# CAN.net
KiCad netlist of a schematic drawn in Altium Designer
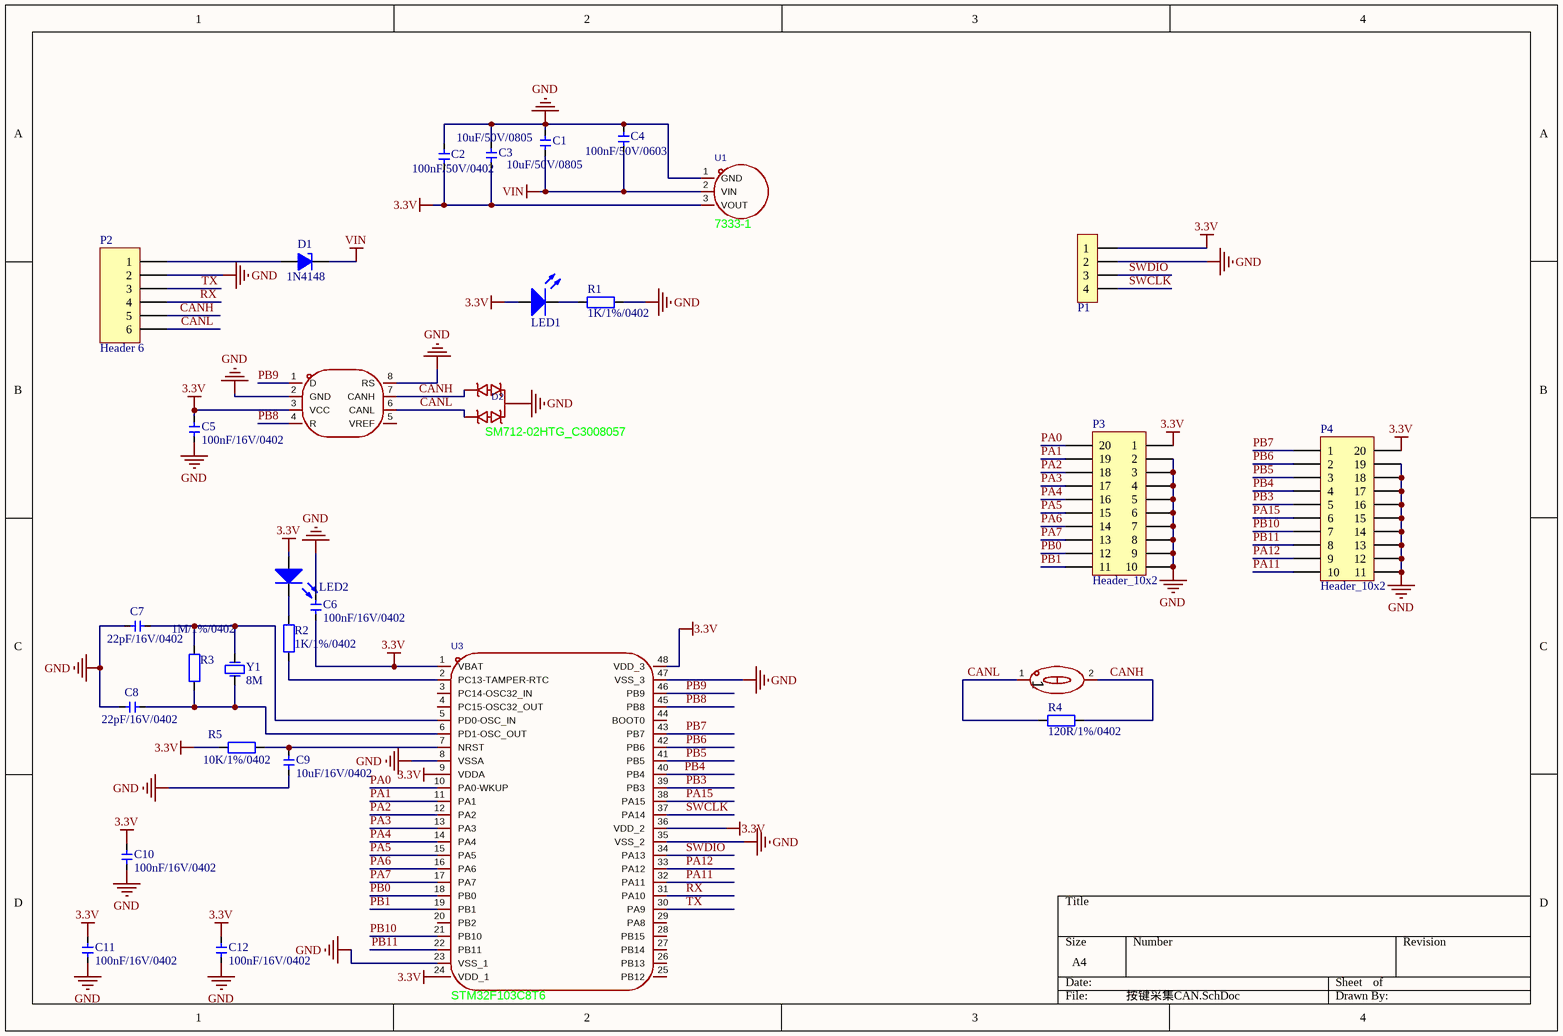
[diagram p0: 按键采集CAN.SchDoc]

(export (version "E")
  (design (tool "Eeschema 10.0.6"))
  (components
    (comp (ref "C1")
      (value "10uF/50V/0805")
      (footprint "CAP-0805")
      (description "无极性电容")
      (fields (field (name "PUBLISHER") "Altium Limited"))
      (libsource (lib "Arrowy_Racing") (part "Cap"))
    )
    (comp (ref "C2")
      (value "100nF/50V/0402")
      (footprint "0402")
      (description "无极性电容")
      (fields (field (name "PUBLISHER") "Altium Limited"))
      (libsource (lib "Arrowy_Racing") (part "Cap"))
    )
    (comp (ref "C3")
      (value "10uF/50V/0805")
      (footprint "CAP-0805")
      (description "无极性电容")
      (fields (field (name "PUBLISHER") "Altium Limited"))
      (libsource (lib "Arrowy_Racing") (part "Cap"))
    )
    (comp (ref "C4")
      (value "100nF/50V/0603")
      (footprint "CAP-0603")
      (description "无极性电容")
      (fields (field (name "PUBLISHER") "Altium Limited"))
      (libsource (lib "Arrowy_Racing") (part "Cap"))
    )
    (comp (ref "C5")
      (value "100nF/16V/0402")
      (footprint "cap-0402")
      (description "无极性电容")
      (fields (field (name "PUBLISHER") "Altium Limited"))
      (libsource (lib "Arrowy_Racing") (part "Cap"))
    )
    (comp (ref "C6")
      (value "100nF/16V/0402")
      (footprint "cap-0402")
      (description "无极性电容")
      (fields (field (name "PUBLISHER") "Altium Limited"))
      (libsource (lib "Arrowy_Racing") (part "Cap"))
    )
    (comp (ref "C7")
      (value "22pF/16V/0402")
      (footprint "cap-0402")
      (description "无极性电容")
      (fields (field (name "PUBLISHER") "Altium Limited"))
      (libsource (lib "Arrowy_Racing") (part "Cap"))
    )
    (comp (ref "C8")
      (value "22pF/16V/0402")
      (footprint "cap-0402")
      (description "无极性电容")
      (fields (field (name "PUBLISHER") "Altium Limited"))
      (libsource (lib "Arrowy_Racing") (part "Cap"))
    )
    (comp (ref "C9")
      (value "10uF/16V/0402")
      (footprint "cap-0402")
      (description "无极性电容")
      (fields (field (name "PUBLISHER") "Altium Limited"))
      (libsource (lib "Arrowy_Racing") (part "Cap"))
    )
    (comp (ref "C10")
      (value "100nF/16V/0402")
      (footprint "cap-0402")
      (description "无极性电容")
      (fields (field (name "PUBLISHER") "Altium Limited"))
      (libsource (lib "Arrowy_Racing") (part "Cap"))
    )
    (comp (ref "C11")
      (value "100nF/16V/0402")
      (footprint "cap-0402")
      (description "无极性电容")
      (fields (field (name "PUBLISHER") "Altium Limited"))
      (libsource (lib "Arrowy_Racing") (part "Cap"))
    )
    (comp (ref "C12")
      (value "100nF/16V/0402")
      (footprint "cap-0402")
      (description "无极性电容")
      (fields (field (name "PUBLISHER") "Altium Limited"))
      (libsource (lib "Arrowy_Racing") (part "Cap"))
    )
    (comp (ref "D1")
      (value "1N4148")
      (footprint "SOD-123")
      (fields (field (name "PUBLISHER") "Altium Limited"))
      (libsource (lib "Arrowy_Racing") (part "Diode-Z"))
    )
    (comp (ref "D2")
      (value "SM712-02HTG_C3008057")
      (footprint "SOT-23-3_L2.9-W1.3-P1.90-LS2.4-BR")
      (libsource (lib "altium-import") (part "root_0_SM712-02HTG_C3008057_"))
    )
    (comp (ref "LED1")
      (value "red")
      (footprint "LED_0603")
      (description "发光二极管")
      (fields (field (name "PUBLISHER") "Altium Limited"))
      (libsource (lib "Arrowy_Racing") (part "LED"))
    )
    (comp (ref "LED2")
      (value "green")
      (footprint "LED_0603")
      (description "发光二极管")
      (fields (field (name "PUBLISHER") "Altium Limited"))
      (libsource (lib "Arrowy_Racing") (part "LED"))
    )
    (comp (ref "P1")
      (value "Header 4")
      (footprint "HDR-SMD_4P-P2.54-H-M-W13.3-N")
      (description "接插件")
      (fields (field (name "PUBLISHER") "Altium Limited"))
      (libsource (lib "Arrowy_Racing") (part "Header 4"))
    )
    (comp (ref "P2")
      (value "Header 6")
      (footprint "CONN-TH_6P-P2.50_HC-XH-6AW-G")
      (description "Header, 6-Pin")
      (fields (field (name "PUBLISHER") "Altium Limited"))
      (libsource (lib "Miscellaneous Connectors") (part "Header 6"))
    )
    (comp (ref "P3")
      (value "Header_10x2")
      (footprint "HDR-TH_20P-P2.54-V-M-R2-C10-S2.54")
      (description "接插件")
      (libsource (lib "Arrowy_Racing") (part "Header_10x2"))
    )
    (comp (ref "P4")
      (value "Header_10x2")
      (footprint "HDR-TH_20P-P2.54-V-M-R2-C10-S2.54")
      (description "接插件")
      (libsource (lib "") (part "Header_10x2_1"))
    )
    (comp (ref "R1")
      (value "1K/1%/0402")
      (footprint "r0402")
      (description "贴片电阻")
      (fields (field (name "PUBLISHER") "Altium Limited"))
      (libsource (lib "Arrowy_Racing") (part "Res"))
    )
    (comp (ref "R2")
      (value "1K/1%/0402")
      (footprint "r0402")
      (description "贴片电阻")
      (fields (field (name "PUBLISHER") "Altium Limited"))
      (libsource (lib "") (part "Res_2"))
    )
    (comp (ref "R3")
      (value "1M/1%/0402")
      (footprint "r0402")
      (description "贴片电阻")
      (fields (field (name "PUBLISHER") "Altium Limited"))
      (libsource (lib "") (part "Res_2"))
    )
    (comp (ref "R4")
      (value "120R/1%/0402")
      (footprint "r0402")
      (description "贴片电阻")
      (fields (field (name "PUBLISHER") "Altium Limited"))
      (libsource (lib "") (part "Res_1"))
    )
    (comp (ref "R5")
      (value "10K/1%/0402")
      (footprint "r0402")
      (description "贴片电阻")
      (fields (field (name "PUBLISHER") "Altium Limited"))
      (libsource (lib "Arrowy_Racing") (part "Res"))
    )
    (comp (ref "SW1")
      (value "DSIC01LS-P_C600988")
      (footprint "SW-SMD_2P-L3.5-W6.1-P2.54-LS9.8")
      (libsource (lib "altium-import") (part "root_3_DSIC01LS-P_C600988_"))
    )
    (comp (ref "U1")
      (value "7333-1")
      (footprint "SOT89")
      (libsource (lib "altium-import") (part "root_0_7333-1_"))
    )
    (comp (ref "U2")
      (value "SN65HVD230DR")
      (footprint "SOIC-8_L4.9-W3.9-P1.27-LS6.0-BL")
      (libsource (lib "altium-import") (part "root_0_SN65HVD230DR_"))
    )
    (comp (ref "U3")
      (value "STM32F103C8T6")
      (footprint "LQFP48_STM32F103C")
      (libsource (lib "altium-import") (part "root_0_STM32F103C8T6_"))
    )
    (comp (ref "Y1")
      (value "8M")
      (footprint "CRYSTAL-SMD_L5.0-W3.2")
      (description "两脚无源晶振")
      (fields (field (name "Comment") "TAXM8M2QLFCDT1T") (field (name "PUBLISHER") "Altium Limited"))
      (libsource (lib "Arrowy_Racing") (part "Passive_Crystal_2Pin"))
    )
  )
  (nets
    (net (code "1") (name "/CANH") (class "Default")
      (node (ref "D2") (pin "1") (pinfunction "1_1") (pintype "passive"))
      (node (ref "P2") (pin "5") (pinfunction "5_5") (pintype "passive"))
      (node (ref "R4") (pin "2") (pinfunction "2_2") (pintype "passive"))
      (node (ref "SW1") (pin "2") (pinfunction "PIN2_2") (pintype "passive"))
      (node (ref "U2") (pin "7") (pinfunction "CANH_7") (pintype "passive"))
    )
    (net (code "2") (name "/CANL") (class "Default")
      (node (ref "D2") (pin "2") (pinfunction "2_2") (pintype "passive"))
      (node (ref "P2") (pin "6") (pinfunction "6_6") (pintype "passive"))
      (node (ref "R4") (pin "1") (pinfunction "1_1") (pintype "passive"))
      (node (ref "SW1") (pin "1") (pinfunction "PIN1_1") (pintype "passive"))
      (node (ref "U2") (pin "6") (pinfunction "CANL_6") (pintype "passive"))
    )
    (net (code "3") (name "/PA0") (class "Default")
      (node (ref "P3") (pin "20") (pinfunction "20_20") (pintype "passive"))
      (node (ref "U3") (pin "10") (pinfunction "PA0-WKUP_10") (pintype "passive"))
    )
    (net (code "4") (name "/PA1") (class "Default")
      (node (ref "P3") (pin "19") (pinfunction "19_19") (pintype "passive"))
      (node (ref "U3") (pin "11") (pinfunction "PA1_11") (pintype "passive"))
    )
    (net (code "5") (name "/PA2") (class "Default")
      (node (ref "P3") (pin "18") (pinfunction "18_18") (pintype "passive"))
      (node (ref "U3") (pin "12") (pinfunction "PA2_12") (pintype "passive"))
    )
    (net (code "6") (name "/PA3") (class "Default")
      (node (ref "P3") (pin "17") (pinfunction "17_17") (pintype "passive"))
      (node (ref "U3") (pin "13") (pinfunction "PA3_13") (pintype "passive"))
    )
    (net (code "7") (name "/PA4") (class "Default")
      (node (ref "P3") (pin "16") (pinfunction "16_16") (pintype "passive"))
      (node (ref "U3") (pin "14") (pinfunction "PA4_14") (pintype "passive"))
    )
    (net (code "8") (name "/PA5") (class "Default")
      (node (ref "P3") (pin "15") (pinfunction "15_15") (pintype "passive"))
      (node (ref "U3") (pin "15") (pinfunction "PA5_15") (pintype "passive"))
    )
    (net (code "9") (name "/PA6") (class "Default")
      (node (ref "P3") (pin "14") (pinfunction "14_14") (pintype "passive"))
      (node (ref "U3") (pin "16") (pinfunction "PA6_16") (pintype "passive"))
    )
    (net (code "10") (name "/PA7") (class "Default")
      (node (ref "P3") (pin "13") (pinfunction "13_13") (pintype "passive"))
      (node (ref "U3") (pin "17") (pinfunction "PA7_17") (pintype "passive"))
    )
    (net (code "11") (name "/PA11") (class "Default")
      (node (ref "P4") (pin "10") (pinfunction "10_10") (pintype "passive"))
      (node (ref "U3") (pin "32") (pinfunction "PA11_32") (pintype "passive"))
    )
    (net (code "12") (name "/PA12") (class "Default")
      (node (ref "P4") (pin "9") (pinfunction "9_9") (pintype "passive"))
      (node (ref "U3") (pin "33") (pinfunction "PA12_33") (pintype "passive"))
    )
    (net (code "13") (name "/PA15") (class "Default")
      (node (ref "P4") (pin "6") (pinfunction "6_6") (pintype "passive"))
      (node (ref "U3") (pin "38") (pinfunction "PA15_38") (pintype "passive"))
    )
    (net (code "14") (name "/PB0") (class "Default")
      (node (ref "P3") (pin "12") (pinfunction "12_12") (pintype "passive"))
      (node (ref "U3") (pin "18") (pinfunction "PB0_18") (pintype "passive"))
    )
    (net (code "15") (name "/PB1") (class "Default")
      (node (ref "P3") (pin "11") (pinfunction "11_11") (pintype "passive"))
      (node (ref "U3") (pin "19") (pinfunction "PB1_19") (pintype "passive"))
    )
    (net (code "16") (name "/PB3") (class "Default")
      (node (ref "P4") (pin "5") (pinfunction "5_5") (pintype "passive"))
      (node (ref "U3") (pin "39") (pinfunction "PB3_39") (pintype "passive"))
    )
    (net (code "17") (name "/PB4") (class "Default")
      (node (ref "P4") (pin "4") (pinfunction "4_4") (pintype "passive"))
      (node (ref "U3") (pin "40") (pinfunction "PB4_40") (pintype "passive"))
    )
    (net (code "18") (name "/PB5") (class "Default")
      (node (ref "P4") (pin "3") (pinfunction "3_3") (pintype "passive"))
      (node (ref "U3") (pin "41") (pinfunction "PB5_41") (pintype "passive"))
    )
    (net (code "19") (name "/PB6") (class "Default")
      (node (ref "P4") (pin "2") (pinfunction "2_2") (pintype "passive"))
      (node (ref "U3") (pin "42") (pinfunction "PB6_42") (pintype "passive"))
    )
    (net (code "20") (name "/PB7") (class "Default")
      (node (ref "P4") (pin "1") (pinfunction "1_1") (pintype "passive"))
      (node (ref "U3") (pin "43") (pinfunction "PB7_43") (pintype "passive"))
    )
    (net (code "21") (name "/PB8") (class "Default")
      (node (ref "U2") (pin "4") (pinfunction "R_4") (pintype "passive"))
      (node (ref "U3") (pin "45") (pinfunction "PB8_45") (pintype "passive"))
    )
    (net (code "22") (name "/PB9") (class "Default")
      (node (ref "U2") (pin "1") (pinfunction "D_1") (pintype "passive"))
      (node (ref "U3") (pin "46") (pinfunction "PB9_46") (pintype "passive"))
    )
    (net (code "23") (name "/PB10") (class "Default")
      (node (ref "P4") (pin "7") (pinfunction "7_7") (pintype "passive"))
      (node (ref "U3") (pin "21") (pinfunction "PB10_21") (pintype "passive"))
    )
    (net (code "24") (name "/PB11") (class "Default")
      (node (ref "P4") (pin "8") (pinfunction "8_8") (pintype "passive"))
      (node (ref "U3") (pin "22") (pinfunction "PB11_22") (pintype "passive"))
    )
    (net (code "25") (name "/RX") (class "Default")
      (node (ref "P2") (pin "4") (pinfunction "4_4") (pintype "passive"))
      (node (ref "U3") (pin "31") (pinfunction "PA10_31") (pintype "passive"))
    )
    (net (code "26") (name "/SWCLK") (class "Default")
      (node (ref "P1") (pin "4") (pinfunction "4_4") (pintype "passive"))
      (node (ref "U3") (pin "37") (pinfunction "PA14_37") (pintype "passive"))
    )
    (net (code "27") (name "/SWDIO") (class "Default")
      (node (ref "P1") (pin "3") (pinfunction "3_3") (pintype "passive"))
      (node (ref "U3") (pin "34") (pinfunction "PA13_34") (pintype "passive"))
    )
    (net (code "28") (name "/TX") (class "Default")
      (node (ref "P2") (pin "3") (pinfunction "3_3") (pintype "passive"))
      (node (ref "U3") (pin "30") (pinfunction "PA9_30") (pintype "passive"))
    )
    (net (code "29") (name "3.3V") (class "Default")
      (node (ref "C10") (pin "1") (pinfunction "1_1") (pintype "passive"))
      (node (ref "C11") (pin "1") (pinfunction "1_1") (pintype "passive"))
      (node (ref "C12") (pin "1") (pinfunction "1_1") (pintype "passive"))
      (node (ref "C2") (pin "1") (pinfunction "1_1") (pintype "passive"))
      (node (ref "C3") (pin "2") (pinfunction "2_2") (pintype "passive"))
      (node (ref "C5") (pin "1") (pinfunction "1_1") (pintype "passive"))
      (node (ref "C6") (pin "2") (pinfunction "2_2") (pintype "passive"))
      (node (ref "LED1") (pin "1") (pinfunction "A_1") (pintype "passive"))
      (node (ref "LED2") (pin "1") (pinfunction "A_1") (pintype "passive"))
      (node (ref "P1") (pin "1") (pinfunction "1_1") (pintype "passive"))
      (node (ref "P3") (pin "1") (pinfunction "1_1") (pintype "passive"))
      (node (ref "P4") (pin "20") (pinfunction "20_20") (pintype "passive"))
      (node (ref "R5") (pin "2") (pinfunction "2_2") (pintype "passive"))
      (node (ref "U1") (pin "3") (pinfunction "VOUT_3") (pintype "passive"))
      (node (ref "U2") (pin "3") (pinfunction "VCC_3") (pintype "passive"))
      (node (ref "U3") (pin "1") (pinfunction "VBAT_1") (pintype "passive"))
      (node (ref "U3") (pin "24") (pinfunction "VDD_1_24") (pintype "passive"))
      (node (ref "U3") (pin "36") (pinfunction "VDD_2_36") (pintype "passive"))
      (node (ref "U3") (pin "48") (pinfunction "VDD_3_48") (pintype "passive"))
      (node (ref "U3") (pin "9") (pinfunction "VDDA_9") (pintype "passive"))
    )
    (net (code "30") (name "GND") (class "Default")
      (node (ref "C1") (pin "2") (pinfunction "2_2") (pintype "passive"))
      (node (ref "C10") (pin "2") (pinfunction "2_2") (pintype "passive"))
      (node (ref "C11") (pin "2") (pinfunction "2_2") (pintype "passive"))
      (node (ref "C12") (pin "2") (pinfunction "2_2") (pintype "passive"))
      (node (ref "C2") (pin "2") (pinfunction "2_2") (pintype "passive"))
      (node (ref "C3") (pin "1") (pinfunction "1_1") (pintype "passive"))
      (node (ref "C4") (pin "2") (pinfunction "2_2") (pintype "passive"))
      (node (ref "C5") (pin "2") (pinfunction "2_2") (pintype "passive"))
      (node (ref "C6") (pin "1") (pinfunction "1_1") (pintype "passive"))
      (node (ref "C7") (pin "2") (pinfunction "2_2") (pintype "passive"))
      (node (ref "C8") (pin "2") (pinfunction "2_2") (pintype "passive"))
      (node (ref "C9") (pin "2") (pinfunction "2_2") (pintype "passive"))
      (node (ref "D2") (pin "3") (pinfunction "3_3") (pintype "passive"))
      (node (ref "P1") (pin "2") (pinfunction "2_2") (pintype "passive"))
      (node (ref "P2") (pin "2") (pinfunction "2_2") (pintype "passive"))
      (node (ref "P3") (pin "10") (pinfunction "10_10") (pintype "passive"))
      (node (ref "P3") (pin "2") (pinfunction "2_2") (pintype "passive"))
      (node (ref "P3") (pin "3") (pinfunction "3_3") (pintype "passive"))
      (node (ref "P3") (pin "4") (pinfunction "4_4") (pintype "passive"))
      (node (ref "P3") (pin "5") (pinfunction "5_5") (pintype "passive"))
      (node (ref "P3") (pin "6") (pinfunction "6_6") (pintype "passive"))
      (node (ref "P3") (pin "7") (pinfunction "7_7") (pintype "passive"))
      (node (ref "P3") (pin "8") (pinfunction "8_8") (pintype "passive"))
      (node (ref "P3") (pin "9") (pinfunction "9_9") (pintype "passive"))
      (node (ref "P4") (pin "11") (pinfunction "11_11") (pintype "passive"))
      (node (ref "P4") (pin "12") (pinfunction "12_12") (pintype "passive"))
      (node (ref "P4") (pin "13") (pinfunction "13_13") (pintype "passive"))
      (node (ref "P4") (pin "14") (pinfunction "14_14") (pintype "passive"))
      (node (ref "P4") (pin "15") (pinfunction "15_15") (pintype "passive"))
      (node (ref "P4") (pin "16") (pinfunction "16_16") (pintype "passive"))
      (node (ref "P4") (pin "17") (pinfunction "17_17") (pintype "passive"))
      (node (ref "P4") (pin "18") (pinfunction "18_18") (pintype "passive"))
      (node (ref "P4") (pin "19") (pinfunction "19_19") (pintype "passive"))
      (node (ref "R1") (pin "1") (pinfunction "1_1") (pintype "passive"))
      (node (ref "U1") (pin "1") (pinfunction "GND_1") (pintype "passive"))
      (node (ref "U2") (pin "2") (pinfunction "GND_2") (pintype "passive"))
      (node (ref "U2") (pin "8") (pinfunction "RS_8") (pintype "passive"))
      (node (ref "U3") (pin "23") (pinfunction "VSS_1_23") (pintype "passive"))
      (node (ref "U3") (pin "35") (pinfunction "VSS_2_35") (pintype "passive"))
      (node (ref "U3") (pin "47") (pinfunction "VSS_3_47") (pintype "passive"))
      (node (ref "U3") (pin "8") (pinfunction "VSSA_8") (pintype "passive"))
    )
    (net (code "31") (name "Net-(D1-A)") (class "Default")
      (node (ref "D1") (pin "1") (pinfunction "A_1") (pintype "passive"))
      (node (ref "P2") (pin "1") (pinfunction "1_1") (pintype "passive"))
    )
    (net (code "32") (name "Net-(LED1-K)") (class "Default")
      (node (ref "LED1") (pin "2") (pinfunction "K_2") (pintype "passive"))
      (node (ref "R1") (pin "2") (pinfunction "2_2") (pintype "passive"))
    )
    (net (code "33") (name "Net-(LED2-K)") (class "Default")
      (node (ref "LED2") (pin "2") (pinfunction "K_2") (pintype "passive"))
      (node (ref "R2") (pin "2") (pinfunction "2_2") (pintype "passive"))
    )
    (net (code "34") (name "Net-(U3-NRST)") (class "Default")
      (node (ref "C9") (pin "1") (pinfunction "1_1") (pintype "passive"))
      (node (ref "R5") (pin "1") (pinfunction "1_1") (pintype "passive"))
      (node (ref "U3") (pin "7") (pinfunction "NRST_7") (pintype "passive"))
    )
    (net (code "35") (name "Net-(U3-PC13-TAMPER-RTC)") (class "Default")
      (node (ref "R2") (pin "1") (pinfunction "1_1") (pintype "passive"))
      (node (ref "U3") (pin "2") (pinfunction "PC13-TAMPER-RTC_2") (pintype "passive"))
    )
    (net (code "36") (name "Net-(U3-PD0-OSC_IN)") (class "Default")
      (node (ref "C7") (pin "1") (pinfunction "1_1") (pintype "passive"))
      (node (ref "R3") (pin "2") (pinfunction "2_2") (pintype "passive"))
      (node (ref "U3") (pin "5") (pinfunction "PD0-OSC_IN_5") (pintype "passive"))
      (node (ref "Y1") (pin "1") (pinfunction "1_1") (pintype "passive"))
    )
    (net (code "37") (name "Net-(U3-PD1-OSC_OUT)") (class "Default")
      (node (ref "C8") (pin "1") (pinfunction "1_1") (pintype "passive"))
      (node (ref "R3") (pin "1") (pinfunction "1_1") (pintype "passive"))
      (node (ref "U3") (pin "6") (pinfunction "PD1-OSC_OUT_6") (pintype "passive"))
      (node (ref "Y1") (pin "2") (pinfunction "2_2") (pintype "passive"))
    )
    (net (code "38") (name "VIN") (class "Default")
      (node (ref "C1") (pin "1") (pinfunction "1_1") (pintype "passive"))
      (node (ref "C4") (pin "1") (pinfunction "1_1") (pintype "passive"))
      (node (ref "D1") (pin "2") (pinfunction "K_2") (pintype "passive"))
      (node (ref "U1") (pin "2") (pinfunction "VIN_2") (pintype "passive"))
    )
    (net (code "39") (name "unconnected-(U2-VREF-Pad5)") (class "Default")
      (node (ref "U2") (pin "5") (pinfunction "VREF_5") (pintype "passive"))
    )
    (net (code "40") (name "unconnected-(U3-BOOT0-Pad44)") (class "Default")
      (node (ref "U3") (pin "44") (pinfunction "BOOT0_44") (pintype "passive"))
    )
    (net (code "41") (name "unconnected-(U3-PA8-Pad29)") (class "Default")
      (node (ref "U3") (pin "29") (pinfunction "PA8_29") (pintype "passive"))
    )
    (net (code "42") (name "unconnected-(U3-PB2-Pad20)") (class "Default")
      (node (ref "U3") (pin "20") (pinfunction "PB2_20") (pintype "passive"))
    )
    (net (code "43") (name "unconnected-(U3-PB12-Pad25)") (class "Default")
      (node (ref "U3") (pin "25") (pinfunction "PB12_25") (pintype "passive"))
    )
    (net (code "44") (name "unconnected-(U3-PB13-Pad26)") (class "Default")
      (node (ref "U3") (pin "26") (pinfunction "PB13_26") (pintype "passive"))
    )
    (net (code "45") (name "unconnected-(U3-PB14-Pad27)") (class "Default")
      (node (ref "U3") (pin "27") (pinfunction "PB14_27") (pintype "passive"))
    )
    (net (code "46") (name "unconnected-(U3-PB15-Pad28)") (class "Default")
      (node (ref "U3") (pin "28") (pinfunction "PB15_28") (pintype "passive"))
    )
    (net (code "47") (name "unconnected-(U3-PC14-OSC32_IN-Pad3)") (class "Default")
      (node (ref "U3") (pin "3") (pinfunction "PC14-OSC32_IN_3") (pintype "passive"))
    )
    (net (code "48") (name "unconnected-(U3-PC15-OSC32_OUT-Pad4)") (class "Default")
      (node (ref "U3") (pin "4") (pinfunction "PC15-OSC32_OUT_4") (pintype "passive"))
    )
  )
)
